# dram_arduino_adapter.net
KiCad netlist of a schematic drawn in EAGLE
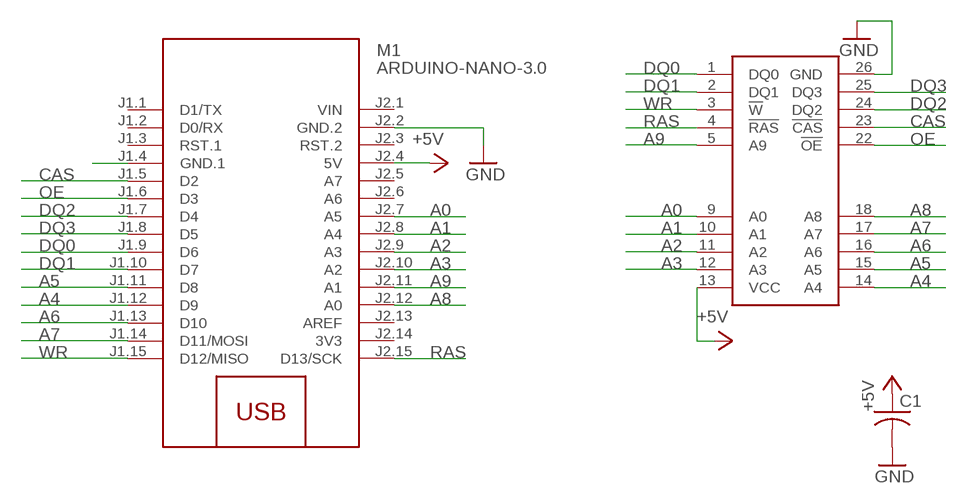
[diagram p0: schematic, sheet 1]

(export (version "E")
  (design (tool "Eeschema 10.0.6"))
  (components
    (comp (ref "C1")
      (value "C-USC1206")
      (footprint "eagle-import:C1206")
      (libsource (lib "eagle-import") (part "C-USC1206"))
    )
    (comp (ref "M1")
      (value "ARDUINO-NANO-3.0")
      (footprint "eagle-import:ARDUINO-NANO-3.0")
      (libsource (lib "eagle-import") (part "ARDUINO-NANO-3.0"))
    )
    (comp (ref "U$1")
      (value "HY514400A")
      (footprint "eagle-import:HY514400A")
      (libsource (lib "eagle-import") (part "HY514400A"))
    )
  )
  (nets
    (net (code "1") (name "+5V") (class "Default")
      (node (ref "C1") (pin "1") (pinfunction "1_1") (pintype "passive"))
      (node (ref "M1") (pin "J2.4") (pinfunction "5V_J2.4") (pintype "power_in"))
      (node (ref "U$1") (pin "13") (pinfunction "VCC_13") (pintype "bidirectional"))
    )
    (net (code "2") (name "/3V3") (class "Default")
      (node (ref "M1") (pin "J2.14") (pinfunction "3V3_J2.14") (pintype "power_in"))
    )
    (net (code "3") (name "/A0") (class "Default")
      (node (ref "M1") (pin "J2.7") (pinfunction "A5_J2.7") (pintype "bidirectional"))
      (node (ref "U$1") (pin "9") (pinfunction "A0_9") (pintype "bidirectional"))
    )
    (net (code "4") (name "/A1") (class "Default")
      (node (ref "M1") (pin "J2.8") (pinfunction "A4_J2.8") (pintype "bidirectional"))
      (node (ref "U$1") (pin "10") (pinfunction "A1_10") (pintype "bidirectional"))
    )
    (net (code "5") (name "/A2") (class "Default")
      (node (ref "M1") (pin "J2.9") (pinfunction "A3_J2.9") (pintype "bidirectional"))
      (node (ref "U$1") (pin "11") (pinfunction "A2_11") (pintype "bidirectional"))
    )
    (net (code "6") (name "/A3") (class "Default")
      (node (ref "M1") (pin "J2.10") (pinfunction "A2_J2.10") (pintype "bidirectional"))
      (node (ref "U$1") (pin "12") (pinfunction "A3_12") (pintype "bidirectional"))
    )
    (net (code "7") (name "/A4") (class "Default")
      (node (ref "M1") (pin "J1.12") (pinfunction "D9_J1.12") (pintype "bidirectional"))
      (node (ref "U$1") (pin "14") (pinfunction "A4_14") (pintype "bidirectional"))
    )
    (net (code "8") (name "/A5") (class "Default")
      (node (ref "M1") (pin "J1.11") (pinfunction "D8_J1.11") (pintype "bidirectional"))
      (node (ref "U$1") (pin "15") (pinfunction "A5_15") (pintype "bidirectional"))
    )
    (net (code "9") (name "/A6") (class "Default")
      (node (ref "M1") (pin "J1.13") (pinfunction "D10_J1.13") (pintype "bidirectional"))
      (node (ref "U$1") (pin "16") (pinfunction "A6_16") (pintype "bidirectional"))
    )
    (net (code "10") (name "/A7") (class "Default")
      (node (ref "M1") (pin "J1.14") (pinfunction "D11/MOSI_J1.14") (pintype "bidirectional"))
      (node (ref "U$1") (pin "17") (pinfunction "A7_17") (pintype "bidirectional"))
    )
    (net (code "11") (name "/A8") (class "Default")
      (node (ref "M1") (pin "J2.12") (pinfunction "A0_J2.12") (pintype "bidirectional"))
      (node (ref "U$1") (pin "18") (pinfunction "A8_18") (pintype "bidirectional"))
    )
    (net (code "12") (name "/A9") (class "Default")
      (node (ref "M1") (pin "J2.11") (pinfunction "A1_J2.11") (pintype "bidirectional"))
      (node (ref "U$1") (pin "5") (pinfunction "A9_5") (pintype "bidirectional"))
    )
    (net (code "13") (name "/CAS") (class "Default")
      (node (ref "M1") (pin "J1.5") (pinfunction "D2_J1.5") (pintype "bidirectional"))
      (node (ref "U$1") (pin "23") (pinfunction "~{CAS}_23") (pintype "bidirectional"))
    )
    (net (code "14") (name "/DQ0") (class "Default")
      (node (ref "M1") (pin "J1.9") (pinfunction "D6_J1.9") (pintype "bidirectional"))
      (node (ref "U$1") (pin "1") (pinfunction "DQ0_1") (pintype "bidirectional"))
    )
    (net (code "15") (name "/DQ1") (class "Default")
      (node (ref "M1") (pin "J1.10") (pinfunction "D7_J1.10") (pintype "bidirectional"))
      (node (ref "U$1") (pin "2") (pinfunction "DQ1_2") (pintype "bidirectional"))
    )
    (net (code "16") (name "/DQ2") (class "Default")
      (node (ref "M1") (pin "J1.7") (pinfunction "D4_J1.7") (pintype "bidirectional"))
      (node (ref "U$1") (pin "24") (pinfunction "DQ2_24") (pintype "bidirectional"))
    )
    (net (code "17") (name "/DQ3") (class "Default")
      (node (ref "M1") (pin "J1.8") (pinfunction "D5_J1.8") (pintype "bidirectional"))
      (node (ref "U$1") (pin "25") (pinfunction "DQ3_25") (pintype "bidirectional"))
    )
    (net (code "18") (name "/OE") (class "Default")
      (node (ref "M1") (pin "J1.6") (pinfunction "D3_J1.6") (pintype "bidirectional"))
      (node (ref "U$1") (pin "22") (pinfunction "~{OE}_22") (pintype "bidirectional"))
    )
    (net (code "19") (name "/RAS") (class "Default")
      (node (ref "M1") (pin "J2.15") (pinfunction "D13/SCK_J2.15") (pintype "bidirectional"))
      (node (ref "U$1") (pin "4") (pinfunction "~{RAS}_4") (pintype "bidirectional"))
    )
    (net (code "20") (name "/VIN") (class "Default")
      (node (ref "M1") (pin "J2.1") (pinfunction "VIN_J2.1") (pintype "power_in"))
    )
    (net (code "21") (name "/WR") (class "Default")
      (node (ref "M1") (pin "J1.15") (pinfunction "D12/MISO_J1.15") (pintype "bidirectional"))
      (node (ref "U$1") (pin "3") (pinfunction "~{W}_3") (pintype "bidirectional"))
    )
    (net (code "22") (name "GND") (class "Default")
      (node (ref "C1") (pin "2") (pinfunction "2_2") (pintype "passive"))
      (node (ref "M1") (pin "J2.2") (pinfunction "GND.2_J2.2") (pintype "power_in"))
      (node (ref "U$1") (pin "26") (pinfunction "GND_26") (pintype "bidirectional"))
    )
    (net (code "23") (name "unconnected-(M1-A6-PadJ2.6)") (class "Default")
      (node (ref "M1") (pin "J2.6") (pinfunction "A6_J2.6") (pintype "bidirectional"))
    )
    (net (code "24") (name "unconnected-(M1-A7-PadJ2.5)") (class "Default")
      (node (ref "M1") (pin "J2.5") (pinfunction "A7_J2.5") (pintype "bidirectional"))
    )
    (net (code "25") (name "unconnected-(M1-AREF-PadJ2.13)") (class "Default")
      (node (ref "M1") (pin "J2.13") (pinfunction "AREF_J2.13") (pintype "bidirectional"))
    )
    (net (code "26") (name "unconnected-(M1-D0{slash}RX-PadJ1.2)") (class "Default")
      (node (ref "M1") (pin "J1.2") (pinfunction "D0/RX_J1.2") (pintype "bidirectional"))
    )
    (net (code "27") (name "unconnected-(M1-D1{slash}TX-PadJ1.1)") (class "Default")
      (node (ref "M1") (pin "J1.1") (pinfunction "D1/TX_J1.1") (pintype "bidirectional"))
    )
    (net (code "28") (name "unconnected-(M1-GND.1-PadJ1.4)") (class "Default")
      (node (ref "M1") (pin "J1.4") (pinfunction "GND.1_J1.4") (pintype "power_in"))
    )
    (net (code "29") (name "unconnected-(M1-RST.1-PadJ1.3)") (class "Default")
      (node (ref "M1") (pin "J1.3") (pinfunction "RST.1_J1.3") (pintype "bidirectional"))
    )
    (net (code "30") (name "unconnected-(M1-RST.2-PadJ2.3)") (class "Default")
      (node (ref "M1") (pin "J2.3") (pinfunction "RST.2_J2.3") (pintype "bidirectional"))
    )
  )
)
